# dekatron-sim-4017.net
KiCad netlist of a schematic drawn in EAGLE
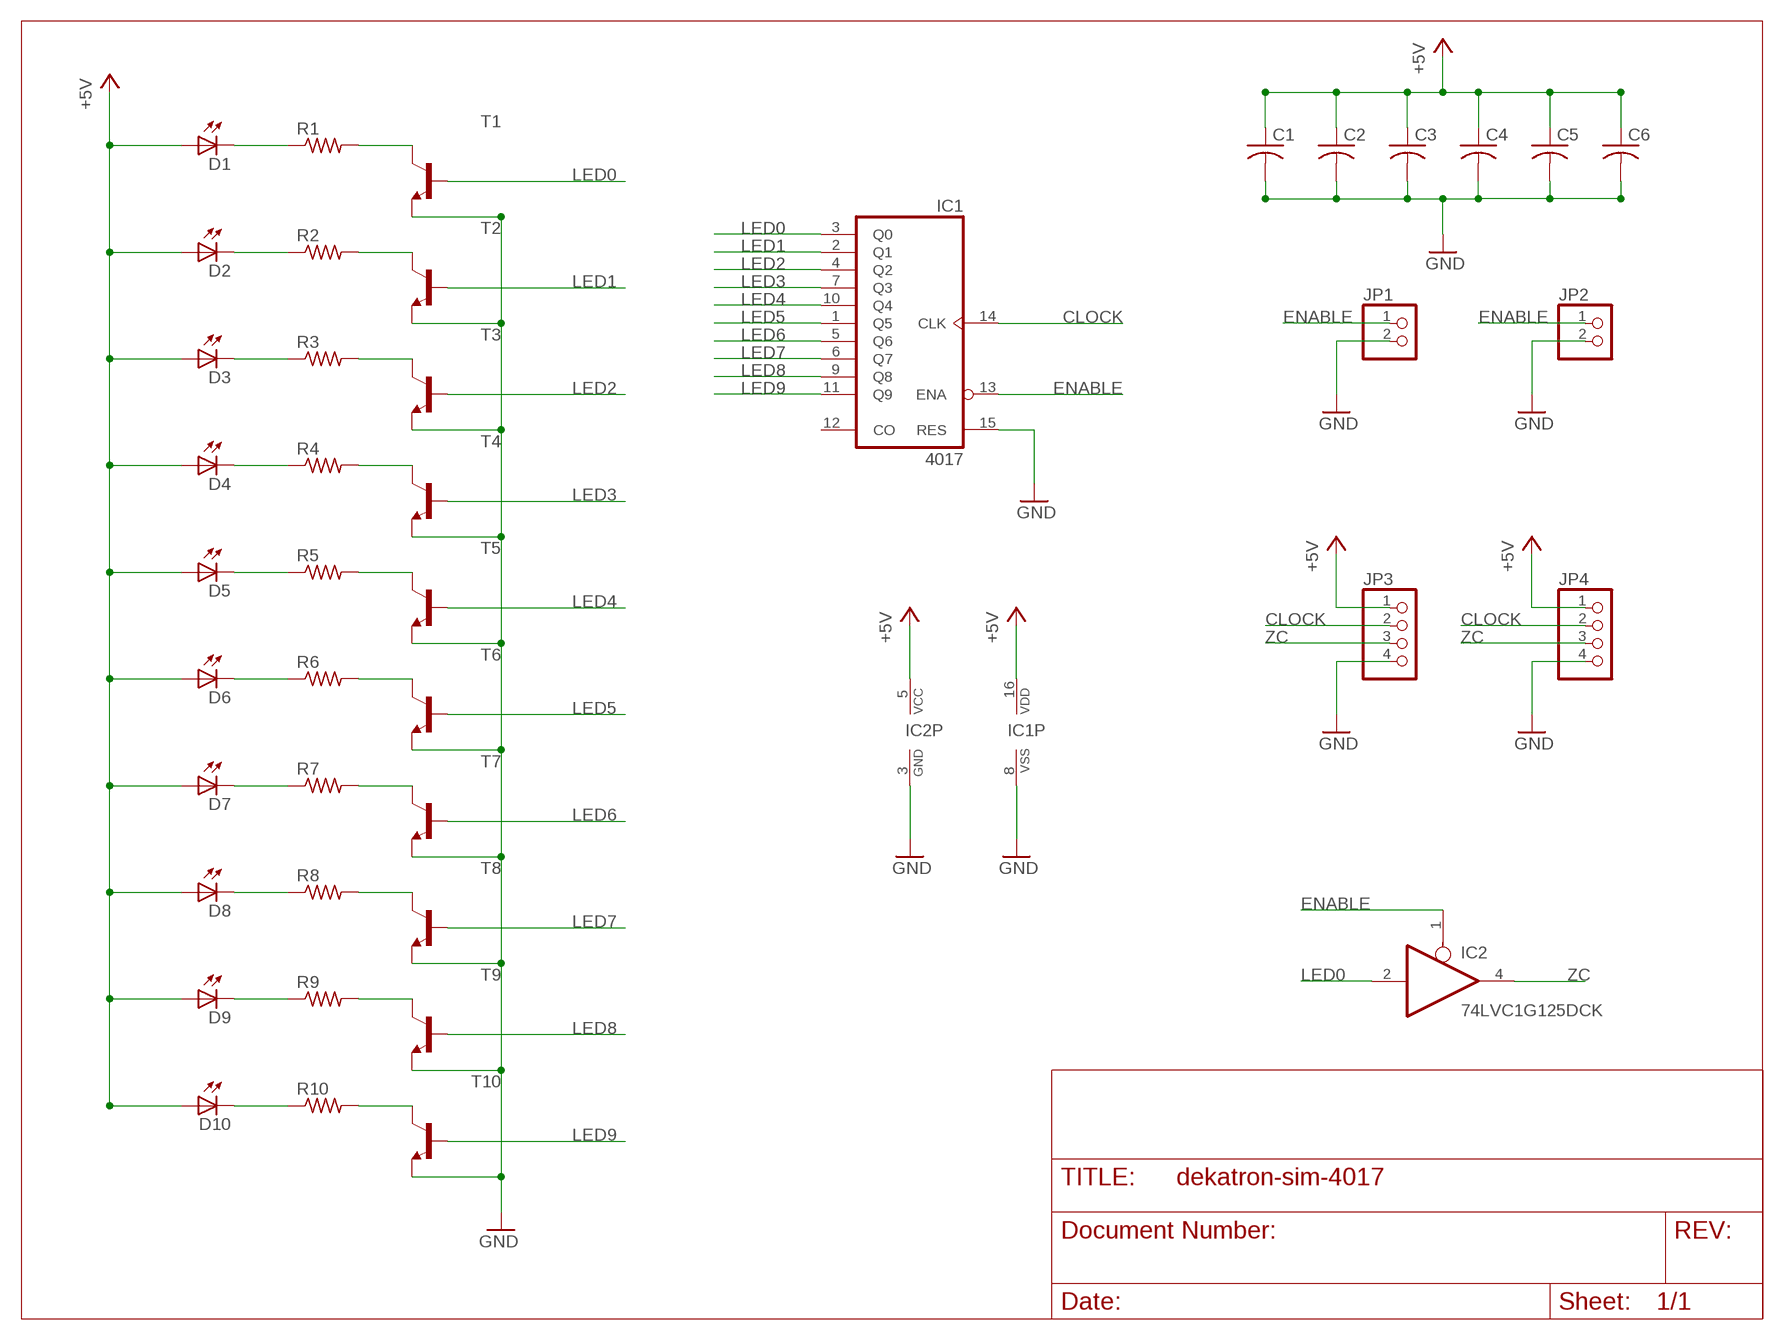
[diagram p0: schematic, sheet 1]

(export (version "E")
  (design (tool "Eeschema 10.0.6"))
  (components
    (comp (ref "C1")
      (value "C-USC0805")
      (footprint "eagle-import:C0805")
      (libsource (lib "eagle-import") (part "C-USC0805"))
    )
    (comp (ref "C2")
      (value "C-USC0805")
      (footprint "eagle-import:C0805")
      (libsource (lib "eagle-import") (part "C-USC0805"))
    )
    (comp (ref "C3")
      (value "C-USC0805")
      (footprint "eagle-import:C0805")
      (libsource (lib "eagle-import") (part "C-USC0805"))
    )
    (comp (ref "C4")
      (value "C-USC0805")
      (footprint "eagle-import:C0805")
      (libsource (lib "eagle-import") (part "C-USC0805"))
    )
    (comp (ref "C5")
      (value "C-USC0805")
      (footprint "eagle-import:C0805")
      (libsource (lib "eagle-import") (part "C-USC0805"))
    )
    (comp (ref "C6")
      (value "C-USC0805")
      (footprint "eagle-import:C0805")
      (libsource (lib "eagle-import") (part "C-USC0805"))
    )
    (comp (ref "D1")
      (value "RED")
      (footprint "eagle-import:CHIP-LED0603")
      (libsource (lib "eagle-import") (part "LEDCHIP-LED0603"))
    )
    (comp (ref "D2")
      (value "RED")
      (footprint "eagle-import:CHIP-LED0603")
      (libsource (lib "eagle-import") (part "LEDCHIP-LED0603"))
    )
    (comp (ref "D3")
      (value "RED")
      (footprint "eagle-import:CHIP-LED0603")
      (libsource (lib "eagle-import") (part "LEDCHIP-LED0603"))
    )
    (comp (ref "D4")
      (value "RED")
      (footprint "eagle-import:CHIP-LED0603")
      (libsource (lib "eagle-import") (part "LEDCHIP-LED0603"))
    )
    (comp (ref "D5")
      (value "RED")
      (footprint "eagle-import:CHIP-LED0603")
      (libsource (lib "eagle-import") (part "LEDCHIP-LED0603"))
    )
    (comp (ref "D6")
      (value "RED")
      (footprint "eagle-import:CHIP-LED0603")
      (libsource (lib "eagle-import") (part "LEDCHIP-LED0603"))
    )
    (comp (ref "D7")
      (value "RED")
      (footprint "eagle-import:CHIP-LED0603")
      (libsource (lib "eagle-import") (part "LEDCHIP-LED0603"))
    )
    (comp (ref "D8")
      (value "RED")
      (footprint "eagle-import:CHIP-LED0603")
      (libsource (lib "eagle-import") (part "LEDCHIP-LED0603"))
    )
    (comp (ref "D9")
      (value "RED")
      (footprint "eagle-import:CHIP-LED0603")
      (libsource (lib "eagle-import") (part "LEDCHIP-LED0603"))
    )
    (comp (ref "D10")
      (value "RED")
      (footprint "eagle-import:CHIP-LED0603")
      (libsource (lib "eagle-import") (part "LEDCHIP-LED0603"))
    )
    (comp (ref "IC1")
      (value "4017")
      (footprint "eagle-import:TSSOP16")
      (libsource (lib "eagle-import") (part "4017"))
    )
    (comp (ref "IC2")
      (value "74LVC1G125DCK")
      (footprint "eagle-import:SC70-5")
      (libsource (lib "eagle-import") (part "741G125DCKLVC"))
    )
    (comp (ref "JP1")
      (value "PINHD-1X2")
      (footprint "eagle-import:1X02")
      (libsource (lib "eagle-import") (part "PINHD-1X2"))
    )
    (comp (ref "JP2")
      (value "PINHD-1X2")
      (footprint "eagle-import:1X02")
      (libsource (lib "eagle-import") (part "PINHD-1X2"))
    )
    (comp (ref "JP3")
      (value "PINHD-1X4")
      (footprint "eagle-import:1X04")
      (libsource (lib "eagle-import") (part "PINHD-1X4"))
    )
    (comp (ref "JP4")
      (value "PINHD-1X4")
      (footprint "eagle-import:1X04")
      (libsource (lib "eagle-import") (part "PINHD-1X4"))
    )
    (comp (ref "R1")
      (value "R-US_R0603")
      (footprint "eagle-import:R0603")
      (libsource (lib "eagle-import") (part "R-US_R0603"))
    )
    (comp (ref "R2")
      (value "R-US_R0603")
      (footprint "eagle-import:R0603")
      (libsource (lib "eagle-import") (part "R-US_R0603"))
    )
    (comp (ref "R3")
      (value "R-US_R0603")
      (footprint "eagle-import:R0603")
      (libsource (lib "eagle-import") (part "R-US_R0603"))
    )
    (comp (ref "R4")
      (value "R-US_R0603")
      (footprint "eagle-import:R0603")
      (libsource (lib "eagle-import") (part "R-US_R0603"))
    )
    (comp (ref "R5")
      (value "R-US_R0603")
      (footprint "eagle-import:R0603")
      (libsource (lib "eagle-import") (part "R-US_R0603"))
    )
    (comp (ref "R6")
      (value "R-US_R0603")
      (footprint "eagle-import:R0603")
      (libsource (lib "eagle-import") (part "R-US_R0603"))
    )
    (comp (ref "R7")
      (value "R-US_R0603")
      (footprint "eagle-import:R0603")
      (libsource (lib "eagle-import") (part "R-US_R0603"))
    )
    (comp (ref "R8")
      (value "R-US_R0603")
      (footprint "eagle-import:R0603")
      (libsource (lib "eagle-import") (part "R-US_R0603"))
    )
    (comp (ref "R9")
      (value "R-US_R0603")
      (footprint "eagle-import:R0603")
      (libsource (lib "eagle-import") (part "R-US_R0603"))
    )
    (comp (ref "R10")
      (value "R-US_R0603")
      (footprint "eagle-import:R0603")
      (libsource (lib "eagle-import") (part "R-US_R0603"))
    )
    (comp (ref "T1")
      (value "MMBT2222ALT1-NPN-SOT23-BEC")
      (footprint "eagle-import:SOT23-BEC")
      (libsource (lib "eagle-import") (part "-NPN-SOT23-BECMMBT2222ALT1"))
    )
    (comp (ref "T2")
      (value "MMBT2222ALT1-NPN-SOT23-BEC")
      (footprint "eagle-import:SOT23-BEC")
      (libsource (lib "eagle-import") (part "-NPN-SOT23-BECMMBT2222ALT1"))
    )
    (comp (ref "T3")
      (value "MMBT2222ALT1-NPN-SOT23-BEC")
      (footprint "eagle-import:SOT23-BEC")
      (libsource (lib "eagle-import") (part "-NPN-SOT23-BECMMBT2222ALT1"))
    )
    (comp (ref "T4")
      (value "MMBT2222ALT1-NPN-SOT23-BEC")
      (footprint "eagle-import:SOT23-BEC")
      (libsource (lib "eagle-import") (part "-NPN-SOT23-BECMMBT2222ALT1"))
    )
    (comp (ref "T5")
      (value "MMBT2222ALT1-NPN-SOT23-BEC")
      (footprint "eagle-import:SOT23-BEC")
      (libsource (lib "eagle-import") (part "-NPN-SOT23-BECMMBT2222ALT1"))
    )
    (comp (ref "T6")
      (value "MMBT2222ALT1-NPN-SOT23-BEC")
      (footprint "eagle-import:SOT23-BEC")
      (libsource (lib "eagle-import") (part "-NPN-SOT23-BECMMBT2222ALT1"))
    )
    (comp (ref "T7")
      (value "MMBT2222ALT1-NPN-SOT23-BEC")
      (footprint "eagle-import:SOT23-BEC")
      (libsource (lib "eagle-import") (part "-NPN-SOT23-BECMMBT2222ALT1"))
    )
    (comp (ref "T8")
      (value "MMBT2222ALT1-NPN-SOT23-BEC")
      (footprint "eagle-import:SOT23-BEC")
      (libsource (lib "eagle-import") (part "-NPN-SOT23-BECMMBT2222ALT1"))
    )
    (comp (ref "T9")
      (value "MMBT2222ALT1-NPN-SOT23-BEC")
      (footprint "eagle-import:SOT23-BEC")
      (libsource (lib "eagle-import") (part "-NPN-SOT23-BECMMBT2222ALT1"))
    )
    (comp (ref "T10")
      (value "MMBT2222ALT1-NPN-SOT23-BEC")
      (footprint "eagle-import:SOT23-BEC")
      (libsource (lib "eagle-import") (part "-NPN-SOT23-BECMMBT2222ALT1"))
    )
  )
  (nets
    (net (code "1") (name "+5V") (class "Default")
      (node (ref "C1") (pin "1") (pinfunction "1_1") (pintype "passive"))
      (node (ref "C2") (pin "1") (pinfunction "1_1") (pintype "passive"))
      (node (ref "C3") (pin "1") (pinfunction "1_1") (pintype "passive"))
      (node (ref "C4") (pin "1") (pinfunction "1_1") (pintype "passive"))
      (node (ref "C5") (pin "1") (pinfunction "1_1") (pintype "passive"))
      (node (ref "C6") (pin "1") (pinfunction "1_1") (pintype "passive"))
      (node (ref "D1") (pin "A") (pinfunction "A_A") (pintype "passive"))
      (node (ref "D10") (pin "A") (pinfunction "A_A") (pintype "passive"))
      (node (ref "D2") (pin "A") (pinfunction "A_A") (pintype "passive"))
      (node (ref "D3") (pin "A") (pinfunction "A_A") (pintype "passive"))
      (node (ref "D4") (pin "A") (pinfunction "A_A") (pintype "passive"))
      (node (ref "D5") (pin "A") (pinfunction "A_A") (pintype "passive"))
      (node (ref "D6") (pin "A") (pinfunction "A_A") (pintype "passive"))
      (node (ref "D7") (pin "A") (pinfunction "A_A") (pintype "passive"))
      (node (ref "D8") (pin "A") (pinfunction "A_A") (pintype "passive"))
      (node (ref "D9") (pin "A") (pinfunction "A_A") (pintype "passive"))
      (node (ref "IC1") (pin "16") (pinfunction "VDD_16") (pintype "power_in"))
      (node (ref "IC2") (pin "5") (pinfunction "VCC_5") (pintype "power_in"))
      (node (ref "JP3") (pin "1") (pinfunction "1_1") (pintype "passive"))
      (node (ref "JP4") (pin "1") (pinfunction "1_1") (pintype "passive"))
    )
    (net (code "2") (name "/CLOCK") (class "Default")
      (node (ref "IC1") (pin "14") (pinfunction "CLK_14") (pintype "input"))
      (node (ref "JP3") (pin "2") (pinfunction "2_2") (pintype "passive"))
      (node (ref "JP4") (pin "2") (pinfunction "2_2") (pintype "passive"))
    )
    (net (code "3") (name "/ENABLE") (class "Default")
      (node (ref "IC1") (pin "13") (pinfunction "ENA_13") (pintype "input"))
      (node (ref "IC2") (pin "1") (pinfunction "OE_1") (pintype "input"))
      (node (ref "JP1") (pin "1") (pinfunction "1_1") (pintype "passive"))
      (node (ref "JP2") (pin "1") (pinfunction "1_1") (pintype "passive"))
    )
    (net (code "4") (name "/LED0") (class "Default")
      (node (ref "IC1") (pin "3") (pinfunction "Q0_3") (pintype "output"))
      (node (ref "IC2") (pin "2") (pinfunction "I_2") (pintype "input"))
      (node (ref "T1") (pin "B") (pinfunction "B_B") (pintype "passive"))
    )
    (net (code "5") (name "/LED1") (class "Default")
      (node (ref "IC1") (pin "2") (pinfunction "Q1_2") (pintype "output"))
      (node (ref "T2") (pin "B") (pinfunction "B_B") (pintype "passive"))
    )
    (net (code "6") (name "/LED2") (class "Default")
      (node (ref "IC1") (pin "4") (pinfunction "Q2_4") (pintype "output"))
      (node (ref "T3") (pin "B") (pinfunction "B_B") (pintype "passive"))
    )
    (net (code "7") (name "/LED3") (class "Default")
      (node (ref "IC1") (pin "7") (pinfunction "Q3_7") (pintype "output"))
      (node (ref "T4") (pin "B") (pinfunction "B_B") (pintype "passive"))
    )
    (net (code "8") (name "/LED4") (class "Default")
      (node (ref "IC1") (pin "10") (pinfunction "Q4_10") (pintype "output"))
      (node (ref "T5") (pin "B") (pinfunction "B_B") (pintype "passive"))
    )
    (net (code "9") (name "/LED5") (class "Default")
      (node (ref "IC1") (pin "1") (pinfunction "Q5_1") (pintype "output"))
      (node (ref "T6") (pin "B") (pinfunction "B_B") (pintype "passive"))
    )
    (net (code "10") (name "/LED6") (class "Default")
      (node (ref "IC1") (pin "5") (pinfunction "Q6_5") (pintype "output"))
      (node (ref "T7") (pin "B") (pinfunction "B_B") (pintype "passive"))
    )
    (net (code "11") (name "/LED7") (class "Default")
      (node (ref "IC1") (pin "6") (pinfunction "Q7_6") (pintype "output"))
      (node (ref "T8") (pin "B") (pinfunction "B_B") (pintype "passive"))
    )
    (net (code "12") (name "/LED8") (class "Default")
      (node (ref "IC1") (pin "9") (pinfunction "Q8_9") (pintype "output"))
      (node (ref "T9") (pin "B") (pinfunction "B_B") (pintype "passive"))
    )
    (net (code "13") (name "/LED9") (class "Default")
      (node (ref "IC1") (pin "11") (pinfunction "Q9_11") (pintype "output"))
      (node (ref "T10") (pin "B") (pinfunction "B_B") (pintype "passive"))
    )
    (net (code "14") (name "/ZC") (class "Default")
      (node (ref "IC2") (pin "4") (pinfunction "O_4") (pintype "tri_state"))
      (node (ref "JP3") (pin "3") (pinfunction "3_3") (pintype "passive"))
      (node (ref "JP4") (pin "3") (pinfunction "3_3") (pintype "passive"))
    )
    (net (code "15") (name "GND") (class "Default")
      (node (ref "C1") (pin "2") (pinfunction "2_2") (pintype "passive"))
      (node (ref "C2") (pin "2") (pinfunction "2_2") (pintype "passive"))
      (node (ref "C3") (pin "2") (pinfunction "2_2") (pintype "passive"))
      (node (ref "C4") (pin "2") (pinfunction "2_2") (pintype "passive"))
      (node (ref "C5") (pin "2") (pinfunction "2_2") (pintype "passive"))
      (node (ref "C6") (pin "2") (pinfunction "2_2") (pintype "passive"))
      (node (ref "IC1") (pin "15") (pinfunction "RES_15") (pintype "input"))
      (node (ref "IC1") (pin "8") (pinfunction "VSS_8") (pintype "power_in"))
      (node (ref "IC2") (pin "3") (pinfunction "GND_3") (pintype "power_in"))
      (node (ref "JP1") (pin "2") (pinfunction "2_2") (pintype "passive"))
      (node (ref "JP2") (pin "2") (pinfunction "2_2") (pintype "passive"))
      (node (ref "JP3") (pin "4") (pinfunction "4_4") (pintype "passive"))
      (node (ref "JP4") (pin "4") (pinfunction "4_4") (pintype "passive"))
      (node (ref "T1") (pin "E") (pinfunction "E_E") (pintype "passive"))
      (node (ref "T10") (pin "E") (pinfunction "E_E") (pintype "passive"))
      (node (ref "T2") (pin "E") (pinfunction "E_E") (pintype "passive"))
      (node (ref "T3") (pin "E") (pinfunction "E_E") (pintype "passive"))
      (node (ref "T4") (pin "E") (pinfunction "E_E") (pintype "passive"))
      (node (ref "T5") (pin "E") (pinfunction "E_E") (pintype "passive"))
      (node (ref "T6") (pin "E") (pinfunction "E_E") (pintype "passive"))
      (node (ref "T7") (pin "E") (pinfunction "E_E") (pintype "passive"))
      (node (ref "T8") (pin "E") (pinfunction "E_E") (pintype "passive"))
      (node (ref "T9") (pin "E") (pinfunction "E_E") (pintype "passive"))
    )
    (net (code "16") (name "Net-(D1-PadC)") (class "Default")
      (node (ref "D1") (pin "C") (pinfunction "C_C") (pintype "passive"))
      (node (ref "R1") (pin "1") (pinfunction "1_1") (pintype "passive"))
    )
    (net (code "17") (name "Net-(D2-PadC)") (class "Default")
      (node (ref "D2") (pin "C") (pinfunction "C_C") (pintype "passive"))
      (node (ref "R2") (pin "1") (pinfunction "1_1") (pintype "passive"))
    )
    (net (code "18") (name "Net-(D3-PadC)") (class "Default")
      (node (ref "D3") (pin "C") (pinfunction "C_C") (pintype "passive"))
      (node (ref "R3") (pin "1") (pinfunction "1_1") (pintype "passive"))
    )
    (net (code "19") (name "Net-(D4-PadC)") (class "Default")
      (node (ref "D4") (pin "C") (pinfunction "C_C") (pintype "passive"))
      (node (ref "R4") (pin "1") (pinfunction "1_1") (pintype "passive"))
    )
    (net (code "20") (name "Net-(D5-PadC)") (class "Default")
      (node (ref "D5") (pin "C") (pinfunction "C_C") (pintype "passive"))
      (node (ref "R5") (pin "1") (pinfunction "1_1") (pintype "passive"))
    )
    (net (code "21") (name "Net-(D6-PadC)") (class "Default")
      (node (ref "D6") (pin "C") (pinfunction "C_C") (pintype "passive"))
      (node (ref "R6") (pin "1") (pinfunction "1_1") (pintype "passive"))
    )
    (net (code "22") (name "Net-(D7-PadC)") (class "Default")
      (node (ref "D7") (pin "C") (pinfunction "C_C") (pintype "passive"))
      (node (ref "R7") (pin "1") (pinfunction "1_1") (pintype "passive"))
    )
    (net (code "23") (name "Net-(D8-PadC)") (class "Default")
      (node (ref "D8") (pin "C") (pinfunction "C_C") (pintype "passive"))
      (node (ref "R8") (pin "1") (pinfunction "1_1") (pintype "passive"))
    )
    (net (code "24") (name "Net-(D9-PadC)") (class "Default")
      (node (ref "D9") (pin "C") (pinfunction "C_C") (pintype "passive"))
      (node (ref "R9") (pin "1") (pinfunction "1_1") (pintype "passive"))
    )
    (net (code "25") (name "Net-(D10-PadC)") (class "Default")
      (node (ref "D10") (pin "C") (pinfunction "C_C") (pintype "passive"))
      (node (ref "R10") (pin "1") (pinfunction "1_1") (pintype "passive"))
    )
    (net (code "26") (name "Net-(R1-Pad2)") (class "Default")
      (node (ref "R1") (pin "2") (pinfunction "2_2") (pintype "passive"))
      (node (ref "T1") (pin "C") (pinfunction "C_C") (pintype "passive"))
    )
    (net (code "27") (name "Net-(R2-Pad2)") (class "Default")
      (node (ref "R2") (pin "2") (pinfunction "2_2") (pintype "passive"))
      (node (ref "T2") (pin "C") (pinfunction "C_C") (pintype "passive"))
    )
    (net (code "28") (name "Net-(R3-Pad2)") (class "Default")
      (node (ref "R3") (pin "2") (pinfunction "2_2") (pintype "passive"))
      (node (ref "T3") (pin "C") (pinfunction "C_C") (pintype "passive"))
    )
    (net (code "29") (name "Net-(R4-Pad2)") (class "Default")
      (node (ref "R4") (pin "2") (pinfunction "2_2") (pintype "passive"))
      (node (ref "T4") (pin "C") (pinfunction "C_C") (pintype "passive"))
    )
    (net (code "30") (name "Net-(R5-Pad2)") (class "Default")
      (node (ref "R5") (pin "2") (pinfunction "2_2") (pintype "passive"))
      (node (ref "T5") (pin "C") (pinfunction "C_C") (pintype "passive"))
    )
    (net (code "31") (name "Net-(R6-Pad2)") (class "Default")
      (node (ref "R6") (pin "2") (pinfunction "2_2") (pintype "passive"))
      (node (ref "T6") (pin "C") (pinfunction "C_C") (pintype "passive"))
    )
    (net (code "32") (name "Net-(R7-Pad2)") (class "Default")
      (node (ref "R7") (pin "2") (pinfunction "2_2") (pintype "passive"))
      (node (ref "T7") (pin "C") (pinfunction "C_C") (pintype "passive"))
    )
    (net (code "33") (name "Net-(R8-Pad2)") (class "Default")
      (node (ref "R8") (pin "2") (pinfunction "2_2") (pintype "passive"))
      (node (ref "T8") (pin "C") (pinfunction "C_C") (pintype "passive"))
    )
    (net (code "34") (name "Net-(R9-Pad2)") (class "Default")
      (node (ref "R9") (pin "2") (pinfunction "2_2") (pintype "passive"))
      (node (ref "T9") (pin "C") (pinfunction "C_C") (pintype "passive"))
    )
    (net (code "35") (name "Net-(R10-Pad2)") (class "Default")
      (node (ref "R10") (pin "2") (pinfunction "2_2") (pintype "passive"))
      (node (ref "T10") (pin "C") (pinfunction "C_C") (pintype "passive"))
    )
    (net (code "36") (name "unconnected-(IC1A-CO-Pad12)") (class "Default")
      (node (ref "IC1") (pin "12") (pinfunction "CO_12") (pintype "output"))
    )
  )
)
